# ESP8266-DS18B20.net
KiCad netlist of a schematic drawn in EAGLE
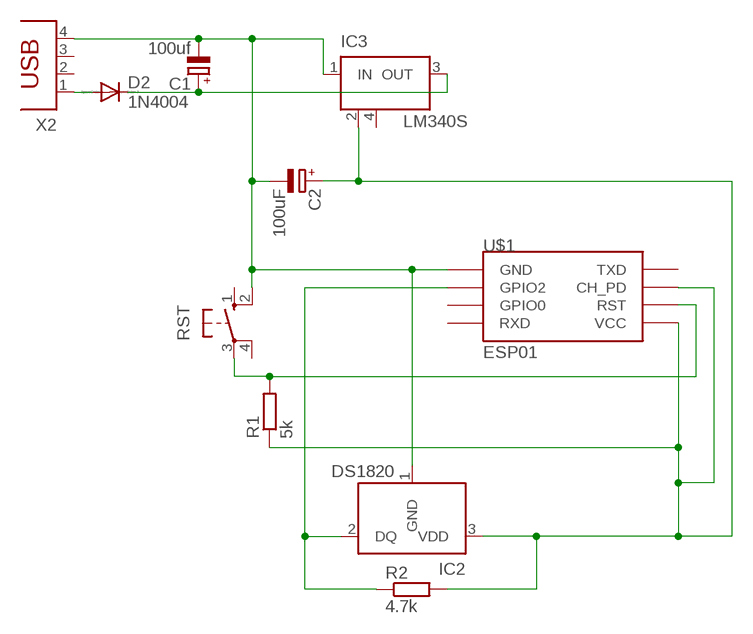
[diagram p0: schematic, sheet 1]

(export (version "E")
  (design (tool "Eeschema 10.0.6"))
  (components
    (comp (ref "C1")
      (value "100uf")
      (footprint "eagle-import:E2,5-5")
      (libsource (lib "eagle-import") (part "CPOL-EUE2.5-5"))
    )
    (comp (ref "C2")
      (value "100uF")
      (footprint "eagle-import:E2,5-5")
      (libsource (lib "eagle-import") (part "CPOL-EUE2.5-5"))
    )
    (comp (ref "D2")
      (value "1N4004")
      (footprint "eagle-import:DO41-10")
      (libsource (lib "eagle-import") (part "1N4004"))
    )
    (comp (ref "IC2")
      (value "DS1820")
      (footprint "eagle-import:TO-92")
      (libsource (lib "eagle-import") (part "DS1820"))
    )
    (comp (ref "IC3")
      (value "LM340S")
      (footprint "eagle-import:SOT223")
      (libsource (lib "eagle-import") (part "LM340S"))
    )
    (comp (ref "R1")
      (value "5k")
      (footprint "eagle-import:0207_12")
      (libsource (lib "eagle-import") (part "R-EU_0207/12"))
    )
    (comp (ref "R2")
      (value "4.7k")
      (footprint "eagle-import:0207_12")
      (libsource (lib "eagle-import") (part "R-EU_0207/12"))
    )
    (comp (ref "RST")
      (value "10-XX")
      (footprint "eagle-import:B3F-10XX")
      (fields (field (name "MPN") "B3F-1000"))
      (libsource (lib "eagle-import") (part "10-XX"))
    )
    (comp (ref "U$1")
      (value "ESP01")
      (footprint "eagle-import:ESP01")
      (libsource (lib "eagle-import") (part "ESP01"))
    )
    (comp (ref "X2")
      (value "PN61729")
      (footprint "eagle-import:PN61729")
      (libsource (lib "eagle-import") (part "PN61729"))
    )
  )
  (nets
    (net (code "1") (name "/5V") (class "Default")
      (node (ref "C1") (pin "+") (pinfunction "+_+") (pintype "passive"))
      (node (ref "D2") (pin "A") (pinfunction "A_A") (pintype "passive"))
      (node (ref "D2") (pin "C") (pinfunction "C_C") (pintype "passive"))
      (node (ref "IC3") (pin "3") (pinfunction "OUT_3") (pintype "passive"))
      (node (ref "X2") (pin "1") (pinfunction "1_1") (pintype "passive"))
    )
    (net (code "2") (name "/GND") (class "Default")
      (node (ref "IC3") (pin "4") (pinfunction "GND_4") (pintype "power_in"))
    )
    (net (code "3") (name "Net-(IC2-DQ)") (class "Default")
      (node (ref "IC2") (pin "2") (pinfunction "DQ_2") (pintype "output"))
      (node (ref "R2") (pin "1") (pinfunction "1_1") (pintype "passive"))
      (node (ref "U$1") (pin "GPIO2") (pinfunction "GPIO2_GPIO2") (pintype "bidirectional"))
    )
    (net (code "4") (name "Net-(IC2-GND)") (class "Default")
      (node (ref "C1") (pin "-") (pinfunction "-_-") (pintype "passive"))
      (node (ref "C2") (pin "-") (pinfunction "-_-") (pintype "passive"))
      (node (ref "IC2") (pin "1") (pinfunction "GND_1") (pintype "power_in"))
      (node (ref "IC3") (pin "1") (pinfunction "IN_1") (pintype "input"))
      (node (ref "RST") (pin "2") (pinfunction "S1_2") (pintype "passive"))
      (node (ref "U$1") (pin "GND") (pinfunction "GND_GND") (pintype "bidirectional"))
      (node (ref "X2") (pin "4") (pinfunction "4_4") (pintype "passive"))
    )
    (net (code "5") (name "Net-(IC2-VDD)") (class "Default")
      (node (ref "C2") (pin "+") (pinfunction "+_+") (pintype "passive"))
      (node (ref "IC2") (pin "3") (pinfunction "VDD_3") (pintype "input"))
      (node (ref "IC3") (pin "2") (pinfunction "GND_2") (pintype "power_in"))
      (node (ref "R1") (pin "1") (pinfunction "1_1") (pintype "passive"))
      (node (ref "R2") (pin "2") (pinfunction "2_2") (pintype "passive"))
      (node (ref "U$1") (pin "CH_PD") (pinfunction "CH_PD_CH_PD") (pintype "bidirectional"))
      (node (ref "U$1") (pin "VCC") (pinfunction "VCC_VCC") (pintype "bidirectional"))
    )
    (net (code "6") (name "Net-(RST-P)") (class "Default")
      (node (ref "R1") (pin "2") (pinfunction "2_2") (pintype "passive"))
      (node (ref "RST") (pin "3") (pinfunction "P_3") (pintype "passive"))
      (node (ref "U$1") (pin "RST") (pinfunction "RST_RST") (pintype "bidirectional"))
    )
    (net (code "7") (name "unconnected-(RST-P1-Pad4)") (class "Default")
      (node (ref "RST") (pin "4") (pinfunction "P1_4") (pintype "passive"))
    )
    (net (code "8") (name "unconnected-(RST-S-Pad1)") (class "Default")
      (node (ref "RST") (pin "1") (pinfunction "S_1") (pintype "passive"))
    )
    (net (code "9") (name "unconnected-(U$1-PadGPIO0)") (class "Default")
      (node (ref "U$1") (pin "GPIO0") (pinfunction "GPIO0_GPIO0") (pintype "bidirectional"))
    )
    (net (code "10") (name "unconnected-(U$1-RXD-PadRX)") (class "Default")
      (node (ref "U$1") (pin "RX") (pinfunction "RXD_RX") (pintype "bidirectional"))
    )
    (net (code "11") (name "unconnected-(U$1-TXD-PadTX)") (class "Default")
      (node (ref "U$1") (pin "TX") (pinfunction "TXD_TX") (pintype "bidirectional"))
    )
    (net (code "12") (name "unconnected-(X2-Pad2)") (class "Default")
      (node (ref "X2") (pin "2") (pinfunction "2_2") (pintype "passive"))
    )
    (net (code "13") (name "unconnected-(X2-Pad3)") (class "Default")
      (node (ref "X2") (pin "3") (pinfunction "3_3") (pintype "passive"))
    )
  )
)
